# ESP8266_P10.net
KiCad netlist of a schematic drawn in EAGLE
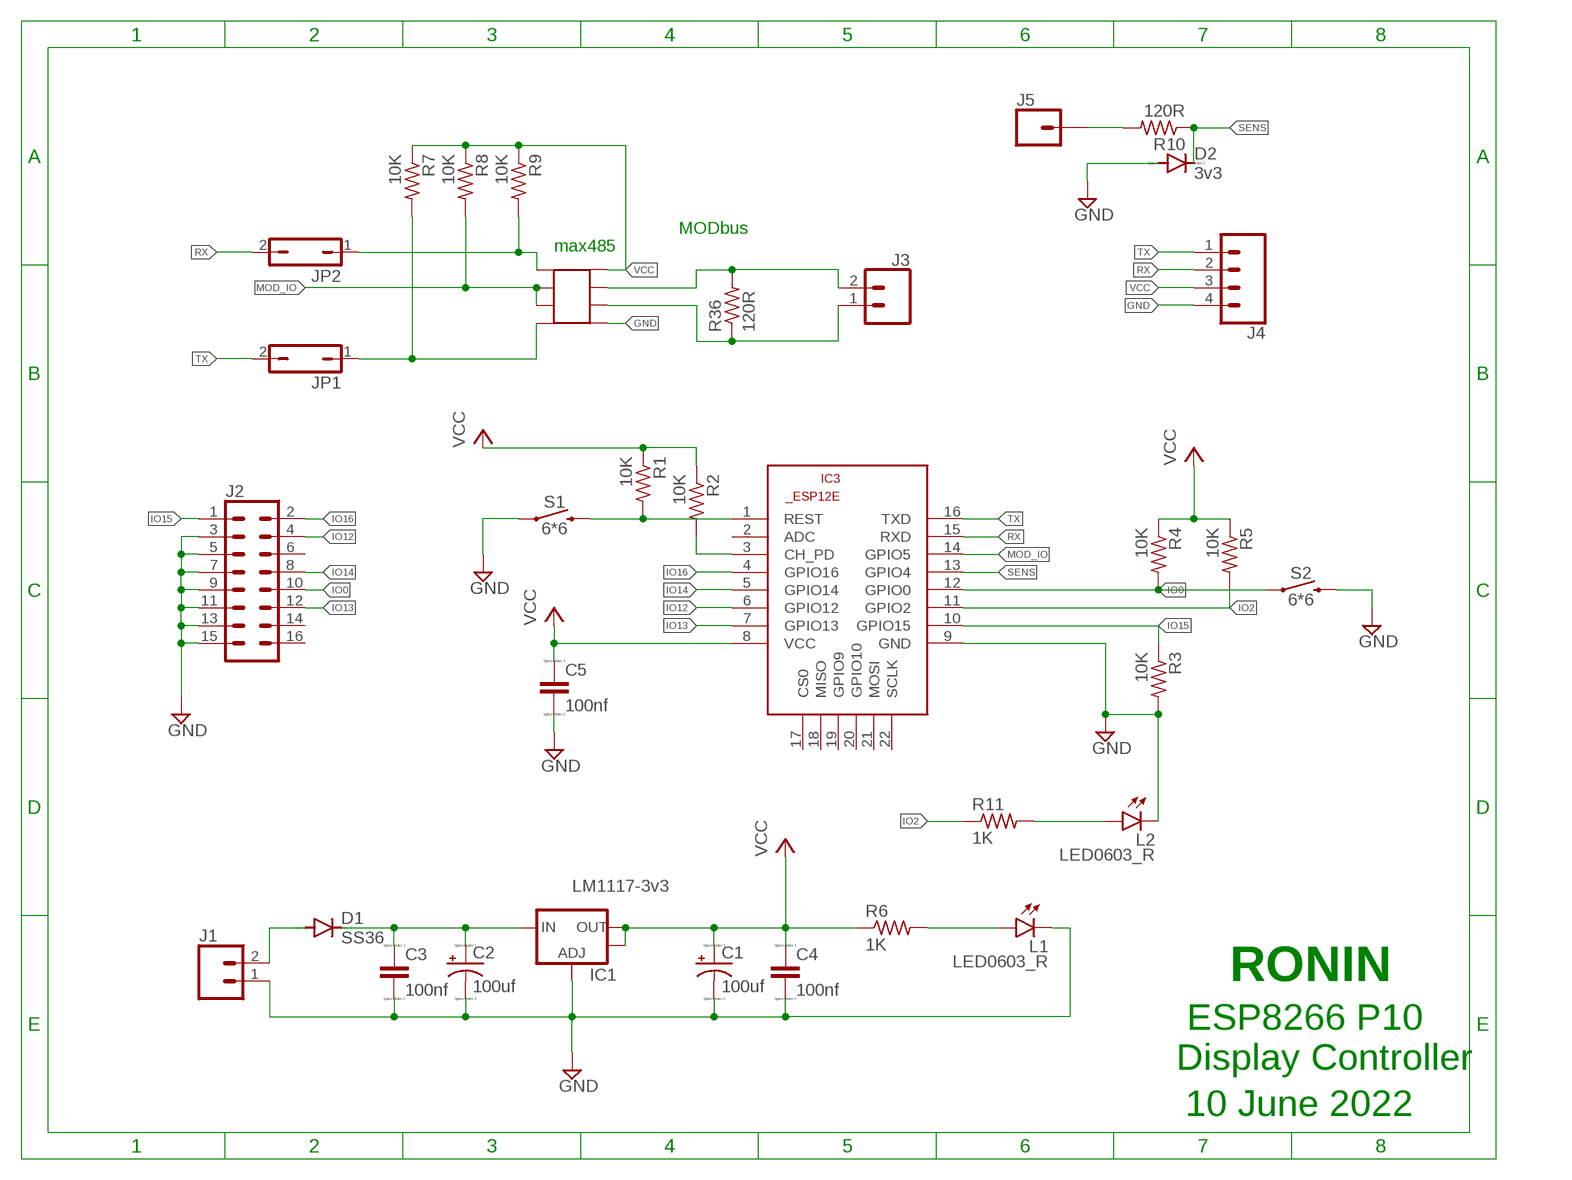
[diagram p0: schematic, sheet 1]

(export (version "E")
  (design (tool "Eeschema 10.0.6"))
  (components
    (comp (ref "C1")
      (value "100uf")
      (footprint "eagle-import:PANASONIC_D")
      (libsource (lib "eagle-import") (part "CAPACITOR_POLD"))
    )
    (comp (ref "C2")
      (value "100uf")
      (footprint "eagle-import:PANASONIC_D")
      (libsource (lib "eagle-import") (part "CAPACITOR_POLD"))
    )
    (comp (ref "C3")
      (value "100nf")
      (footprint "eagle-import:C0603")
      (libsource (lib "eagle-import") (part "CAPACITOR_CER4"))
    )
    (comp (ref "C4")
      (value "100nf")
      (footprint "eagle-import:C0603")
      (libsource (lib "eagle-import") (part "CAPACITOR_CER4"))
    )
    (comp (ref "C5")
      (value "100nf")
      (footprint "eagle-import:C0603")
      (libsource (lib "eagle-import") (part "CAPACITOR_CER4"))
    )
    (comp (ref "D1")
      (value "SS36")
      (footprint "eagle-import:DO-214AC")
      (libsource (lib "eagle-import") (part "DIODEAC2"))
    )
    (comp (ref "D2")
      (value "3v3")
      (footprint "eagle-import:SOD80C")
      (libsource (lib "eagle-import") (part "DIODE80C"))
    )
    (comp (ref "IC1")
      (value "LM1117-3v3")
      (footprint "eagle-import:SOT223")
      (libsource (lib "eagle-import") (part "V_REG_LM1117SOT223"))
    )
    (comp (ref "IC2")
      (value "MAX485")
      (footprint "eagle-import:HSOP-8")
      (libsource (lib "eagle-import") (part "SOP_8"))
    )
    (comp (ref "IC3")
      (value "ESP8266-12EESP12E")
      (footprint "eagle-import:ESP8266-ESP12E")
      (libsource (lib "eagle-import") (part "ESP8266-12EESP12E"))
    )
    (comp (ref "J1")
      (value "CONN_023.5MM")
      (footprint "eagle-import:SCREWTERMINAL-3.5MM-2")
      (libsource (lib "eagle-import") (part "CONN_023.5MM"))
    )
    (comp (ref "J2")
      (value "CONN_08X2")
      (footprint "eagle-import:2X8")
      (libsource (lib "eagle-import") (part "CONN_08X2"))
    )
    (comp (ref "J3")
      (value "CONN_023.5MM-NO_SILK")
      (footprint "eagle-import:SCREWTERMINAL-3.5MM-2-NS")
      (libsource (lib "eagle-import") (part "CONN_023.5MM-NO_SILK"))
    )
    (comp (ref "J4")
      (value "CONN_04")
      (footprint "eagle-import:1X04")
      (libsource (lib "eagle-import") (part "CONN_04"))
    )
    (comp (ref "J5")
      (value "CONN_01")
      (footprint "eagle-import:1X01")
      (libsource (lib "eagle-import") (part "CONN_01"))
    )
    (comp (ref "JP1")
      (value "JP1Q")
      (footprint "eagle-import:JP1")
      (libsource (lib "eagle-import") (part "JP1Q"))
    )
    (comp (ref "JP2")
      (value "JP1Q")
      (footprint "eagle-import:JP1")
      (libsource (lib "eagle-import") (part "JP1Q"))
    )
    (comp (ref "L1")
      (value "LED0603_R")
      (footprint "eagle-import:0603_LED_GREEN")
      (libsource (lib "eagle-import") (part "LED0603_R"))
    )
    (comp (ref "L2")
      (value "LED0603_R")
      (footprint "eagle-import:0603_LED_GREEN")
      (libsource (lib "eagle-import") (part "LED0603_R"))
    )
    (comp (ref "R1")
      (value "10K")
      (footprint "eagle-import:R0603")
      (libsource (lib "eagle-import") (part "RESISTOR0603"))
    )
    (comp (ref "R2")
      (value "10K")
      (footprint "eagle-import:R0603")
      (libsource (lib "eagle-import") (part "RESISTOR0603"))
    )
    (comp (ref "R3")
      (value "10K")
      (footprint "eagle-import:R0603")
      (libsource (lib "eagle-import") (part "RESISTOR0603"))
    )
    (comp (ref "R4")
      (value "10K")
      (footprint "eagle-import:R0603")
      (libsource (lib "eagle-import") (part "RESISTOR0603"))
    )
    (comp (ref "R5")
      (value "10K")
      (footprint "eagle-import:R0603")
      (libsource (lib "eagle-import") (part "RESISTOR0603"))
    )
    (comp (ref "R6")
      (value "1K")
      (footprint "eagle-import:R0603")
      (libsource (lib "eagle-import") (part "RESISTOR0603"))
    )
    (comp (ref "R7")
      (value "10K")
      (footprint "eagle-import:R0603")
      (libsource (lib "eagle-import") (part "RESISTOR0603"))
    )
    (comp (ref "R8")
      (value "10K")
      (footprint "eagle-import:R0603")
      (libsource (lib "eagle-import") (part "RESISTOR0603"))
    )
    (comp (ref "R9")
      (value "10K")
      (footprint "eagle-import:R0603")
      (libsource (lib "eagle-import") (part "RESISTOR0603"))
    )
    (comp (ref "R10")
      (value "120R")
      (footprint "eagle-import:R0603")
      (libsource (lib "eagle-import") (part "RESISTOR0603"))
    )
    (comp (ref "R11")
      (value "1K")
      (footprint "eagle-import:R0603")
      (libsource (lib "eagle-import") (part "RESISTOR0603"))
    )
    (comp (ref "R36")
      (value "120R")
      (footprint "eagle-import:R0603")
      (libsource (lib "eagle-import") (part "RESISTOR0603"))
    )
    (comp (ref "S1")
      (value "6*6")
      (footprint "eagle-import:TACTILE_SWITCH_PTH_6.0MM")
      (libsource (lib "eagle-import") (part "MOMENTARY-SWITCH-SPST-PTH-6.0MM"))
    )
    (comp (ref "S2")
      (value "6*6")
      (footprint "eagle-import:TACTILE_SWITCH_PTH_6.0MM")
      (libsource (lib "eagle-import") (part "MOMENTARY-SWITCH-SPST-PTH-6.0MM"))
    )
  )
  (nets
    (net (code "1") (name "GND") (class "Default")
      (node (ref "C1") (pin "-") (pinfunction "-_-") (pintype "passive"))
      (node (ref "C2") (pin "-") (pinfunction "-_-") (pintype "passive"))
      (node (ref "C3") (pin "2") (pinfunction "2_2") (pintype "passive"))
      (node (ref "C4") (pin "2") (pinfunction "2_2") (pintype "passive"))
      (node (ref "C5") (pin "2") (pinfunction "2_2") (pintype "passive"))
      (node (ref "D2") (pin "A") (pinfunction "A_A") (pintype "passive"))
      (node (ref "IC1") (pin "1") (pinfunction "ADJ_1") (pintype "input"))
      (node (ref "IC2") (pin "5") (pinfunction "5_5") (pintype "bidirectional"))
      (node (ref "IC3") (pin "9") (pinfunction "GND_9") (pintype "bidirectional"))
      (node (ref "J1") (pin "1") (pinfunction "1_1") (pintype "passive"))
      (node (ref "J2") (pin "11") (pinfunction "11_11") (pintype "passive"))
      (node (ref "J2") (pin "13") (pinfunction "13_13") (pintype "passive"))
      (node (ref "J2") (pin "15") (pinfunction "15_15") (pintype "passive"))
      (node (ref "J2") (pin "3") (pinfunction "3_3") (pintype "passive"))
      (node (ref "J2") (pin "5") (pinfunction "5_5") (pintype "passive"))
      (node (ref "J2") (pin "7") (pinfunction "7_7") (pintype "passive"))
      (node (ref "J2") (pin "9") (pinfunction "9_9") (pintype "passive"))
      (node (ref "J4") (pin "4") (pinfunction "4_4") (pintype "passive"))
      (node (ref "L1") (pin "C") (pinfunction "C_C") (pintype "passive"))
      (node (ref "L2") (pin "C") (pinfunction "C_C") (pintype "passive"))
      (node (ref "R3") (pin "2") (pinfunction "2_2") (pintype "passive"))
      (node (ref "S1") (pin "1") (pinfunction "1_1") (pintype "passive"))
      (node (ref "S2") (pin "3") (pinfunction "2_3") (pintype "passive"))
    )
    (net (code "2") (name "IO0") (class "Default")
      (node (ref "IC3") (pin "12") (pinfunction "GPIO0_12") (pintype "bidirectional"))
      (node (ref "J2") (pin "10") (pinfunction "10_10") (pintype "passive"))
      (node (ref "R4") (pin "2") (pinfunction "2_2") (pintype "passive"))
      (node (ref "S2") (pin "1") (pinfunction "1_1") (pintype "passive"))
    )
    (net (code "3") (name "IO2") (class "Default")
      (node (ref "IC3") (pin "11") (pinfunction "GPIO2_11") (pintype "bidirectional"))
      (node (ref "R11") (pin "1") (pinfunction "1_1") (pintype "passive"))
      (node (ref "R5") (pin "2") (pinfunction "2_2") (pintype "passive"))
    )
    (net (code "4") (name "IO12") (class "Default")
      (node (ref "IC3") (pin "6") (pinfunction "GPIO12_6") (pintype "bidirectional"))
      (node (ref "J2") (pin "4") (pinfunction "4_4") (pintype "passive"))
    )
    (net (code "5") (name "IO13") (class "Default")
      (node (ref "IC3") (pin "7") (pinfunction "GPIO13_7") (pintype "bidirectional"))
      (node (ref "J2") (pin "12") (pinfunction "12_12") (pintype "passive"))
    )
    (net (code "6") (name "IO14") (class "Default")
      (node (ref "IC3") (pin "5") (pinfunction "GPIO14_5") (pintype "bidirectional"))
      (node (ref "J2") (pin "8") (pinfunction "8_8") (pintype "passive"))
    )
    (net (code "7") (name "IO15") (class "Default")
      (node (ref "IC3") (pin "10") (pinfunction "GPIO15_10") (pintype "bidirectional"))
      (node (ref "J2") (pin "1") (pinfunction "1_1") (pintype "passive"))
      (node (ref "R3") (pin "1") (pinfunction "1_1") (pintype "passive"))
    )
    (net (code "8") (name "IO16") (class "Default")
      (node (ref "IC3") (pin "4") (pinfunction "GPIO16_4") (pintype "bidirectional"))
      (node (ref "J2") (pin "2") (pinfunction "2_2") (pintype "passive"))
    )
    (net (code "9") (name "MOD_IO") (class "Default")
      (node (ref "IC2") (pin "2") (pinfunction "2_2") (pintype "bidirectional"))
      (node (ref "IC2") (pin "3") (pinfunction "3_3") (pintype "bidirectional"))
      (node (ref "IC3") (pin "14") (pinfunction "GPIO5_14") (pintype "bidirectional"))
      (node (ref "R8") (pin "2") (pinfunction "2_2") (pintype "passive"))
    )
    (net (code "10") (name "Net-(D1-PadA)") (class "Default")
      (node (ref "D1") (pin "A") (pinfunction "A_A") (pintype "passive"))
      (node (ref "J1") (pin "2") (pinfunction "2_2") (pintype "passive"))
    )
    (net (code "11") (name "Net-(IC1-IN)") (class "Default")
      (node (ref "C2") (pin "+") (pinfunction "+_+") (pintype "passive"))
      (node (ref "C3") (pin "1") (pinfunction "1_1") (pintype "passive"))
      (node (ref "D1") (pin "C") (pinfunction "C_C") (pintype "passive"))
      (node (ref "IC1") (pin "3") (pinfunction "IN_3") (pintype "input"))
    )
    (net (code "12") (name "Net-(IC2-Pad1)") (class "Default")
      (node (ref "IC2") (pin "1") (pinfunction "1_1") (pintype "bidirectional"))
      (node (ref "JP2") (pin "1") (pinfunction "1_1") (pintype "passive"))
      (node (ref "R9") (pin "2") (pinfunction "2_2") (pintype "passive"))
    )
    (net (code "13") (name "Net-(IC2-Pad4)") (class "Default")
      (node (ref "IC2") (pin "4") (pinfunction "4_4") (pintype "bidirectional"))
      (node (ref "JP1") (pin "1") (pinfunction "1_1") (pintype "passive"))
      (node (ref "R7") (pin "2") (pinfunction "2_2") (pintype "passive"))
    )
    (net (code "14") (name "Net-(IC2-Pad6)") (class "Default")
      (node (ref "IC2") (pin "6") (pinfunction "6_6") (pintype "bidirectional"))
      (node (ref "J3") (pin "1") (pinfunction "1_1") (pintype "passive"))
      (node (ref "R36") (pin "1") (pinfunction "1_1") (pintype "passive"))
    )
    (net (code "15") (name "Net-(IC2-Pad7)") (class "Default")
      (node (ref "IC2") (pin "7") (pinfunction "7_7") (pintype "bidirectional"))
      (node (ref "J3") (pin "2") (pinfunction "2_2") (pintype "passive"))
      (node (ref "R36") (pin "2") (pinfunction "2_2") (pintype "passive"))
    )
    (net (code "16") (name "Net-(IC3-CH_PD)") (class "Default")
      (node (ref "IC3") (pin "3") (pinfunction "CH_PD_3") (pintype "bidirectional"))
      (node (ref "R2") (pin "2") (pinfunction "2_2") (pintype "passive"))
    )
    (net (code "17") (name "Net-(IC3-REST)") (class "Default")
      (node (ref "IC3") (pin "1") (pinfunction "REST_1") (pintype "bidirectional"))
      (node (ref "R1") (pin "2") (pinfunction "2_2") (pintype "passive"))
      (node (ref "S1") (pin "3") (pinfunction "2_3") (pintype "passive"))
    )
    (net (code "18") (name "Net-(J5-Pad1)") (class "Default")
      (node (ref "J5") (pin "1") (pinfunction "1_1") (pintype "passive"))
      (node (ref "R10") (pin "2") (pinfunction "2_2") (pintype "passive"))
    )
    (net (code "19") (name "Net-(L1-PadA)") (class "Default")
      (node (ref "L1") (pin "A") (pinfunction "A_A") (pintype "passive"))
      (node (ref "R6") (pin "2") (pinfunction "2_2") (pintype "passive"))
    )
    (net (code "20") (name "Net-(L2-PadA)") (class "Default")
      (node (ref "L2") (pin "A") (pinfunction "A_A") (pintype "passive"))
      (node (ref "R11") (pin "2") (pinfunction "2_2") (pintype "passive"))
    )
    (net (code "21") (name "RX") (class "Default")
      (node (ref "IC3") (pin "15") (pinfunction "RXD_15") (pintype "bidirectional"))
      (node (ref "J4") (pin "2") (pinfunction "2_2") (pintype "passive"))
      (node (ref "JP2") (pin "2") (pinfunction "2_2") (pintype "passive"))
    )
    (net (code "22") (name "SENS") (class "Default")
      (node (ref "D2") (pin "C") (pinfunction "C_C") (pintype "passive"))
      (node (ref "IC3") (pin "13") (pinfunction "GPIO4_13") (pintype "bidirectional"))
      (node (ref "R10") (pin "1") (pinfunction "1_1") (pintype "passive"))
    )
    (net (code "23") (name "TX") (class "Default")
      (node (ref "IC3") (pin "16") (pinfunction "TXD_16") (pintype "bidirectional"))
      (node (ref "J4") (pin "1") (pinfunction "1_1") (pintype "passive"))
      (node (ref "JP1") (pin "2") (pinfunction "2_2") (pintype "passive"))
    )
    (net (code "24") (name "VCC") (class "Default")
      (node (ref "C1") (pin "+") (pinfunction "+_+") (pintype "passive"))
      (node (ref "C4") (pin "1") (pinfunction "1_1") (pintype "passive"))
      (node (ref "C5") (pin "1") (pinfunction "1_1") (pintype "passive"))
      (node (ref "IC1") (pin "2") (pinfunction "OUT_2") (pintype "output"))
      (node (ref "IC1") (pin "4") (pinfunction "OUT_4") (pintype "output"))
      (node (ref "IC2") (pin "8") (pinfunction "8_8") (pintype "bidirectional"))
      (node (ref "IC3") (pin "8") (pinfunction "VCC_8") (pintype "bidirectional"))
      (node (ref "J4") (pin "3") (pinfunction "3_3") (pintype "passive"))
      (node (ref "R1") (pin "1") (pinfunction "1_1") (pintype "passive"))
      (node (ref "R2") (pin "1") (pinfunction "1_1") (pintype "passive"))
      (node (ref "R4") (pin "1") (pinfunction "1_1") (pintype "passive"))
      (node (ref "R5") (pin "1") (pinfunction "1_1") (pintype "passive"))
      (node (ref "R6") (pin "1") (pinfunction "1_1") (pintype "passive"))
      (node (ref "R7") (pin "1") (pinfunction "1_1") (pintype "passive"))
      (node (ref "R8") (pin "1") (pinfunction "1_1") (pintype "passive"))
      (node (ref "R9") (pin "1") (pinfunction "1_1") (pintype "passive"))
    )
    (net (code "25") (name "unconnected-(IC3-ADC-Pad2)") (class "Default")
      (node (ref "IC3") (pin "2") (pinfunction "ADC_2") (pintype "bidirectional"))
    )
    (net (code "26") (name "unconnected-(IC3-CS0-Pad17)") (class "Default")
      (node (ref "IC3") (pin "17") (pinfunction "CS0_17") (pintype "bidirectional"))
    )
    (net (code "27") (name "unconnected-(IC3-GPIO9-Pad19)") (class "Default")
      (node (ref "IC3") (pin "19") (pinfunction "GPIO9_19") (pintype "bidirectional"))
    )
    (net (code "28") (name "unconnected-(IC3-GPIO10-Pad20)") (class "Default")
      (node (ref "IC3") (pin "20") (pinfunction "GPIO10_20") (pintype "bidirectional"))
    )
    (net (code "29") (name "unconnected-(IC3-MISO-Pad18)") (class "Default")
      (node (ref "IC3") (pin "18") (pinfunction "MISO_18") (pintype "bidirectional"))
    )
    (net (code "30") (name "unconnected-(IC3-MOSI-Pad21)") (class "Default")
      (node (ref "IC3") (pin "21") (pinfunction "MOSI_21") (pintype "bidirectional"))
    )
    (net (code "31") (name "unconnected-(IC3-SCLK-Pad22)") (class "Default")
      (node (ref "IC3") (pin "22") (pinfunction "SCLK_22") (pintype "bidirectional"))
    )
    (net (code "32") (name "unconnected-(J2-Pad6)") (class "Default")
      (node (ref "J2") (pin "6") (pinfunction "6_6") (pintype "passive"))
    )
    (net (code "33") (name "unconnected-(J2-Pad14)") (class "Default")
      (node (ref "J2") (pin "14") (pinfunction "14_14") (pintype "passive"))
    )
    (net (code "34") (name "unconnected-(J2-Pad16)") (class "Default")
      (node (ref "J2") (pin "16") (pinfunction "16_16") (pintype "passive"))
    )
  )
)
